# 6_-KeyLed.net
KiCad netlist of a schematic drawn in Altium Designer
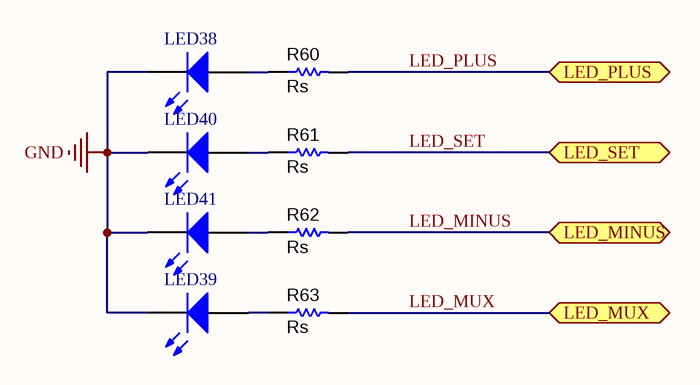
[diagram p0: [6]-KeyLed.SchDoc]

(export (version "E")
  (design (tool "Eeschema 10.0.6"))
  (components
    (comp (ref "LED38")
      (value "LED")
      (footprint "LED-0603-YELLOW")
      (description "Typical INFRARED GaAs LED")
      (fields (field (name "PUBLISHER") "Altium Limited"))
      (libsource (lib "VTEKLib") (part "LED"))
    )
    (comp (ref "LED39")
      (value "LED")
      (footprint "LED-0603-YELLOW")
      (description "Typical INFRARED GaAs LED")
      (fields (field (name "PUBLISHER") "Altium Limited"))
      (libsource (lib "VTEKLib") (part "LED"))
    )
    (comp (ref "LED40")
      (value "LED")
      (footprint "LED-0603-YELLOW")
      (description "Typical INFRARED GaAs LED")
      (fields (field (name "PUBLISHER") "Altium Limited"))
      (libsource (lib "VTEKLib") (part "LED"))
    )
    (comp (ref "LED41")
      (value "LED")
      (footprint "LED-0603-YELLOW")
      (description "Typical INFRARED GaAs LED")
      (fields (field (name "PUBLISHER") "Altium Limited"))
      (libsource (lib "VTEKLib") (part "LED"))
    )
    (comp (ref "R60")
      (value "Rs")
      (footprint "0603")
      (description "RES, 1.00k ohm, 1%, 0.1W, 0603")
      (fields
        (field (name "PARTNUMBER") "CRCW06031K00FKEA")
        (field (name "MANUFACTURER") "Vishay-Dale")
        (field (name "PUBLISHER") "Texas Instruments")
      )
      (libsource (lib "tuongpv2") (part "R0603"))
    )
    (comp (ref "R61")
      (value "Rs")
      (footprint "0603")
      (description "RES, 1.00k ohm, 1%, 0.1W, 0603")
      (fields
        (field (name "PARTNUMBER") "CRCW06031K00FKEA")
        (field (name "MANUFACTURER") "Vishay-Dale")
        (field (name "PUBLISHER") "Texas Instruments")
      )
      (libsource (lib "tuongpv2") (part "R0603"))
    )
    (comp (ref "R62")
      (value "Rs")
      (footprint "0603")
      (description "RES, 1.00k ohm, 1%, 0.1W, 0603")
      (fields
        (field (name "PARTNUMBER") "CRCW06031K00FKEA")
        (field (name "MANUFACTURER") "Vishay-Dale")
        (field (name "PUBLISHER") "Texas Instruments")
      )
      (libsource (lib "tuongpv2") (part "R0603"))
    )
    (comp (ref "R63")
      (value "Rs")
      (footprint "0603")
      (description "RES, 1.00k ohm, 1%, 0.1W, 0603")
      (fields
        (field (name "PARTNUMBER") "CRCW06031K00FKEA")
        (field (name "MANUFACTURER") "Vishay-Dale")
        (field (name "PUBLISHER") "Texas Instruments")
      )
      (libsource (lib "tuongpv2") (part "R0603"))
    )
  )
  (nets
    (net (code "1") (name "/LED_MINUS") (class "Default")
      (node (ref "R62") (pin "2") (pinfunction "2_2") (pintype "passive"))
    )
    (net (code "2") (name "/LED_MUX") (class "Default")
      (node (ref "R63") (pin "2") (pinfunction "2_2") (pintype "passive"))
    )
    (net (code "3") (name "/LED_PLUS") (class "Default")
      (node (ref "R60") (pin "2") (pinfunction "2_2") (pintype "passive"))
    )
    (net (code "4") (name "/LED_SET") (class "Default")
      (node (ref "R61") (pin "2") (pinfunction "2_2") (pintype "passive"))
    )
    (net (code "5") (name "GND") (class "Default")
      (node (ref "LED38") (pin "2") (pinfunction "K_2") (pintype "passive"))
      (node (ref "LED39") (pin "2") (pinfunction "K_2") (pintype "passive"))
      (node (ref "LED40") (pin "2") (pinfunction "K_2") (pintype "passive"))
      (node (ref "LED41") (pin "2") (pinfunction "K_2") (pintype "passive"))
    )
    (net (code "6") (name "Net-(LED38-A)") (class "Default")
      (node (ref "LED38") (pin "1") (pinfunction "A_1") (pintype "passive"))
      (node (ref "R60") (pin "1") (pinfunction "1_1") (pintype "passive"))
    )
    (net (code "7") (name "Net-(LED39-A)") (class "Default")
      (node (ref "LED39") (pin "1") (pinfunction "A_1") (pintype "passive"))
      (node (ref "R63") (pin "1") (pinfunction "1_1") (pintype "passive"))
    )
    (net (code "8") (name "Net-(LED40-A)") (class "Default")
      (node (ref "LED40") (pin "1") (pinfunction "A_1") (pintype "passive"))
      (node (ref "R61") (pin "1") (pinfunction "1_1") (pintype "passive"))
    )
    (net (code "9") (name "Net-(LED41-A)") (class "Default")
      (node (ref "LED41") (pin "1") (pinfunction "A_1") (pintype "passive"))
      (node (ref "R62") (pin "1") (pinfunction "1_1") (pintype "passive"))
    )
  )
)
